# Schematic_ASTRA_UNIT00_2024-12-20.net
KiCad netlist of a schematic drawn in Altium Designer
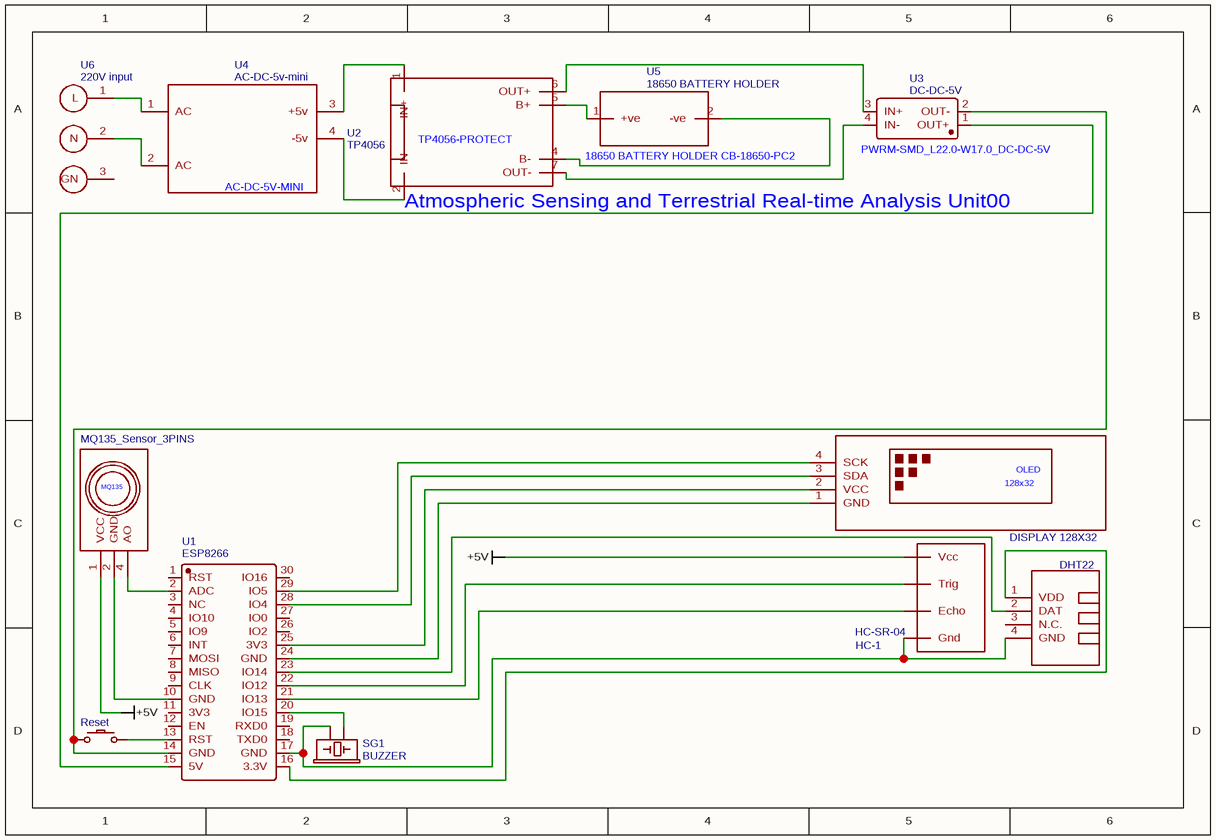
[diagram p0: Schematic_ASTRA_UNIT00_2024-12-20.schdoc]

(export (version "E")
  (design (tool "Eeschema 10.0.6"))
  (components
    (comp (ref "1")
      (value "DISPLAY 128X32")
      (fields (field (name "CONTRIBUTOR") "Neeraj Aggarwal"))
      (libsource (lib "altium-import") (part "root_0_DISPLAY 128X32_"))
    )
    (comp (ref "2")
      (value "DHT22")
      (fields (field (name "CONTRIBUTOR") "Koushik1111"))
      (libsource (lib "altium-import") (part "root_0_DHT22_"))
    )
    (comp (ref "3")
      (value "Reset")
      (fields (field (name "CONTRIBUTOR") "dipaolo.1882662"))
      (libsource (lib "altium-import") (part "root_0_Reset_"))
    )
    (comp (ref "HC-1")
      (value "HC-SR-04")
      (fields (field (name "CONTRIBUTOR") "Malov999"))
      (libsource (lib "altium-import") (part "root_0_HC-SR-04_"))
    )
    (comp (ref "SG1")
      (value "BUZZER")
      (fields (field (name "CONTRIBUTOR") "Daniil-Shteud"))
      (libsource (lib "altium-import") (part "root_3_BUZZER_"))
    )
    (comp (ref "U1")
      (value "ESP8266")
      (fields
        (field (name "MANUFACTURER") "Ai-Thinker(安信可)")
        (field (name "MANUFACTURER PART") "NODEMCU(12F)")
        (field (name "CONTRIBUTOR") "lcsc")
      )
      (libsource (lib "altium-import") (part "root_0_ESP8266_"))
    )
    (comp (ref "U2")
      (value "TP4056")
      (fields (field (name "MANUFACTURER PART") "TP4056-protect") (field (name "CONTRIBUTOR") "James Martin"))
      (libsource (lib "altium-import") (part "root_0_TP4056_"))
    )
    (comp (ref "U3")
      (value "DC-DC-5V")
      (fields (field (name "CONTRIBUTOR") "LCSC"))
      (libsource (lib "altium-import") (part "root_2_DC-DC-5V_"))
    )
    (comp (ref "U4")
      (value "AC-DC-5v-mini")
      (fields (field (name "CONTRIBUTOR") "Prim_2006"))
      (libsource (lib "altium-import") (part "root_0_AC-DC-5v-mini_"))
    )
    (comp (ref "U5")
      (value "18650 BATTERY HOLDER")
      (fields (field (name "CONTRIBUTOR") "wjya _rcr"))
      (libsource (lib "altium-import") (part "root_2_18650 BATTERY HOLDER_"))
    )
    (comp (ref "U6")
      (value "220V input")
      (fields (field (name "CONTRIBUTOR") "paulenaz690"))
      (libsource (lib "altium-import") (part "root_3_220V input_"))
    )
    (comp (ref "U7")
      (value "MQ135_Sensor_3PINS")
      (fields (field (name "CONTRIBUTOR") "Frederico A"))
      (libsource (lib "altium-import") (part "root_0_MQ135_Sensor_3PINS_"))
    )
  )
  (nets
    (net (code "1") (name "+5V") (class "Default")
      (node (ref "HC-1") (pin "VCC") (pinfunction "Vcc_VCC") (pintype "passive"))
      (node (ref "U7") (pin "1") (pinfunction "VCC_1") (pintype "passive"))
    )
    (net (code "2") (name "Net-(1-GND)") (class "Default")
      (node (ref "1") (pin "1") (pinfunction "GND_1") (pintype "passive"))
      (node (ref "U1") (pin "24") (pinfunction "GND_24") (pintype "passive"))
    )
    (net (code "3") (name "Net-(1-SCK)") (class "Default")
      (node (ref "1") (pin "4") (pinfunction "SCK_4") (pintype "passive"))
      (node (ref "U1") (pin "29") (pinfunction "IO5_29") (pintype "passive"))
    )
    (net (code "4") (name "Net-(1-SDA)") (class "Default")
      (node (ref "1") (pin "3") (pinfunction "SDA_3") (pintype "passive"))
      (node (ref "U1") (pin "28") (pinfunction "IO4_28") (pintype "passive"))
    )
    (net (code "5") (name "Net-(1-VCC)") (class "Default")
      (node (ref "1") (pin "2") (pinfunction "VCC_2") (pintype "passive"))
      (node (ref "U1") (pin "25") (pinfunction "3V3_25") (pintype "passive"))
    )
    (net (code "6") (name "Net-(2-DAT)") (class "Default")
      (node (ref "2") (pin "2") (pinfunction "DAT_2") (pintype "passive"))
      (node (ref "U1") (pin "23") (pinfunction "IO14_23") (pintype "passive"))
    )
    (net (code "7") (name "Net-(2-GND)") (class "Default")
      (node (ref "2") (pin "4") (pinfunction "GND_4") (pintype "passive"))
      (node (ref "HC-1") (pin "GND") (pinfunction "Gnd_GND") (pintype "passive"))
      (node (ref "SG1") (pin "-") (pinfunction "2_-") (pintype "passive"))
      (node (ref "U1") (pin "17") (pinfunction "GND_17") (pintype "passive"))
    )
    (net (code "8") (name "Net-(2-VDD)") (class "Default")
      (node (ref "2") (pin "1") (pinfunction "VDD_1") (pintype "passive"))
      (node (ref "U1") (pin "16") (pinfunction "3.3V_16") (pintype "passive"))
    )
    (net (code "9") (name "Net-(3-PadP$ACTIVE)") (class "Default")
      (node (ref "3") (pin "P$ACTIVE") (pinfunction "P$ACTIVE_P$ACTIVE") (pintype "passive"))
      (node (ref "U1") (pin "13") (pinfunction "RST_13") (pintype "passive"))
    )
    (net (code "10") (name "Net-(HC-1-Echo)") (class "Default")
      (node (ref "HC-1") (pin "ECHO") (pinfunction "Echo_ECHO") (pintype "passive"))
      (node (ref "U1") (pin "21") (pinfunction "IO13_21") (pintype "passive"))
    )
    (net (code "11") (name "Net-(HC-1-Trig)") (class "Default")
      (node (ref "HC-1") (pin "TRIG") (pinfunction "Trig_TRIG") (pintype "passive"))
      (node (ref "U1") (pin "22") (pinfunction "IO12_22") (pintype "passive"))
    )
    (net (code "12") (name "Net-(SG1-1)") (class "Default")
      (node (ref "SG1") (pin "+") (pinfunction "1_+") (pintype "passive"))
      (node (ref "U1") (pin "20") (pinfunction "IO15_20") (pintype "passive"))
    )
    (net (code "13") (name "Net-(U1-5V)") (class "Default")
      (node (ref "U1") (pin "15") (pinfunction "5V_15") (pintype "passive"))
      (node (ref "U3") (pin "1") (pinfunction "OUT+_1") (pintype "passive"))
    )
    (net (code "14") (name "Net-(U1-ADC)") (class "Default")
      (node (ref "U1") (pin "2") (pinfunction "ADC_2") (pintype "passive"))
      (node (ref "U7") (pin "4") (pinfunction "AO_4") (pintype "passive"))
    )
    (net (code "15") (name "Net-(U2-B+)") (class "Default")
      (node (ref "U2") (pin "5") (pinfunction "B+_5") (pintype "passive"))
      (node (ref "U5") (pin "1") (pinfunction "+ve_1") (pintype "passive"))
    )
    (net (code "16") (name "Net-(U2-B-)") (class "Default")
      (node (ref "U2") (pin "4") (pinfunction "B-_4") (pintype "passive"))
      (node (ref "U5") (pin "2") (pinfunction "-ve_2") (pintype "passive"))
    )
    (net (code "17") (name "Net-(U2-IN+)") (class "Default")
      (node (ref "U2") (pin "1") (pinfunction "IN+_1") (pintype "passive"))
      (node (ref "U4") (pin "3") (pinfunction "+5v_3") (pintype "passive"))
    )
    (net (code "18") (name "Net-(U2-IN-)") (class "Default")
      (node (ref "U2") (pin "2") (pinfunction "IN-_2") (pintype "passive"))
      (node (ref "U4") (pin "4") (pinfunction "-5v_4") (pintype "passive"))
    )
    (net (code "19") (name "Net-(U2-OUT+)") (class "Default")
      (node (ref "U2") (pin "6") (pinfunction "OUT+_6") (pintype "passive"))
      (node (ref "U3") (pin "3") (pinfunction "IN+_3") (pintype "passive"))
    )
    (net (code "20") (name "Net-(U2-OUT-)") (class "Default")
      (node (ref "U2") (pin "7") (pinfunction "OUT-_7") (pintype "passive"))
      (node (ref "U3") (pin "4") (pinfunction "IN-_4") (pintype "passive"))
    )
    (net (code "21") (name "Net-(U3-OUT-)") (class "Default")
      (node (ref "3") (pin "P$GND") (pinfunction "P$GND_P$GND") (pintype "passive"))
      (node (ref "U1") (pin "14") (pinfunction "GND_14") (pintype "passive"))
      (node (ref "U3") (pin "2") (pinfunction "OUT-_2") (pintype "passive"))
    )
    (net (code "22") (name "Net-(U6-L)") (class "Default")
      (node (ref "U4") (pin "1") (pinfunction "AC_1") (pintype "passive"))
      (node (ref "U6") (pin "1") (pinfunction "L_1") (pintype "passive"))
    )
    (net (code "23") (name "Net-(U6-N)") (class "Default")
      (node (ref "U4") (pin "2") (pinfunction "AC_2") (pintype "passive"))
      (node (ref "U6") (pin "2") (pinfunction "N_2") (pintype "passive"))
    )
    (net (code "24") (name "Net-(U7-GND)") (class "Default")
      (node (ref "U1") (pin "10") (pinfunction "GND_10") (pintype "passive"))
      (node (ref "U7") (pin "2") (pinfunction "GND_2") (pintype "passive"))
    )
    (net (code "25") (name "unconnected-(2-N.C.-Pad3)") (class "Default")
      (node (ref "2") (pin "3") (pinfunction "N.C._3") (pintype "passive"))
    )
    (net (code "26") (name "unconnected-(U1-3V3-Pad11)") (class "Default")
      (node (ref "U1") (pin "11") (pinfunction "3V3_11") (pintype "passive"))
    )
    (net (code "27") (name "unconnected-(U1-CLK-Pad9)") (class "Default")
      (node (ref "U1") (pin "9") (pinfunction "CLK_9") (pintype "passive"))
    )
    (net (code "28") (name "unconnected-(U1-EN-Pad12)") (class "Default")
      (node (ref "U1") (pin "12") (pinfunction "EN_12") (pintype "passive"))
    )
    (net (code "29") (name "unconnected-(U1-INT-Pad6)") (class "Default")
      (node (ref "U1") (pin "6") (pinfunction "INT_6") (pintype "passive"))
    )
    (net (code "30") (name "unconnected-(U1-IO0-Pad27)") (class "Default")
      (node (ref "U1") (pin "27") (pinfunction "IO0_27") (pintype "passive"))
    )
    (net (code "31") (name "unconnected-(U1-IO2-Pad26)") (class "Default")
      (node (ref "U1") (pin "26") (pinfunction "IO2_26") (pintype "passive"))
    )
    (net (code "32") (name "unconnected-(U1-IO9-Pad5)") (class "Default")
      (node (ref "U1") (pin "5") (pinfunction "IO9_5") (pintype "passive"))
    )
    (net (code "33") (name "unconnected-(U1-IO10-Pad4)") (class "Default")
      (node (ref "U1") (pin "4") (pinfunction "IO10_4") (pintype "passive"))
    )
    (net (code "34") (name "unconnected-(U1-IO16-Pad30)") (class "Default")
      (node (ref "U1") (pin "30") (pinfunction "IO16_30") (pintype "passive"))
    )
    (net (code "35") (name "unconnected-(U1-MISO-Pad8)") (class "Default")
      (node (ref "U1") (pin "8") (pinfunction "MISO_8") (pintype "passive"))
    )
    (net (code "36") (name "unconnected-(U1-MOSI-Pad7)") (class "Default")
      (node (ref "U1") (pin "7") (pinfunction "MOSI_7") (pintype "passive"))
    )
    (net (code "37") (name "unconnected-(U1-NC-Pad3)") (class "Default")
      (node (ref "U1") (pin "3") (pinfunction "NC_3") (pintype "passive"))
    )
    (net (code "38") (name "unconnected-(U1-RST-Pad1)") (class "Default")
      (node (ref "U1") (pin "1") (pinfunction "RST_1") (pintype "passive"))
    )
    (net (code "39") (name "unconnected-(U1-RXD0-Pad19)") (class "Default")
      (node (ref "U1") (pin "19") (pinfunction "RXD0_19") (pintype "passive"))
    )
    (net (code "40") (name "unconnected-(U1-TXD0-Pad18)") (class "Default")
      (node (ref "U1") (pin "18") (pinfunction "TXD0_18") (pintype "passive"))
    )
    (net (code "41") (name "unconnected-(U6-GN-Pad3)") (class "Default")
      (node (ref "U6") (pin "3") (pinfunction "GN_3") (pintype "passive"))
    )
  )
)
